# Buzzer_Card.net
KiCad netlist of a schematic drawn in EAGLE
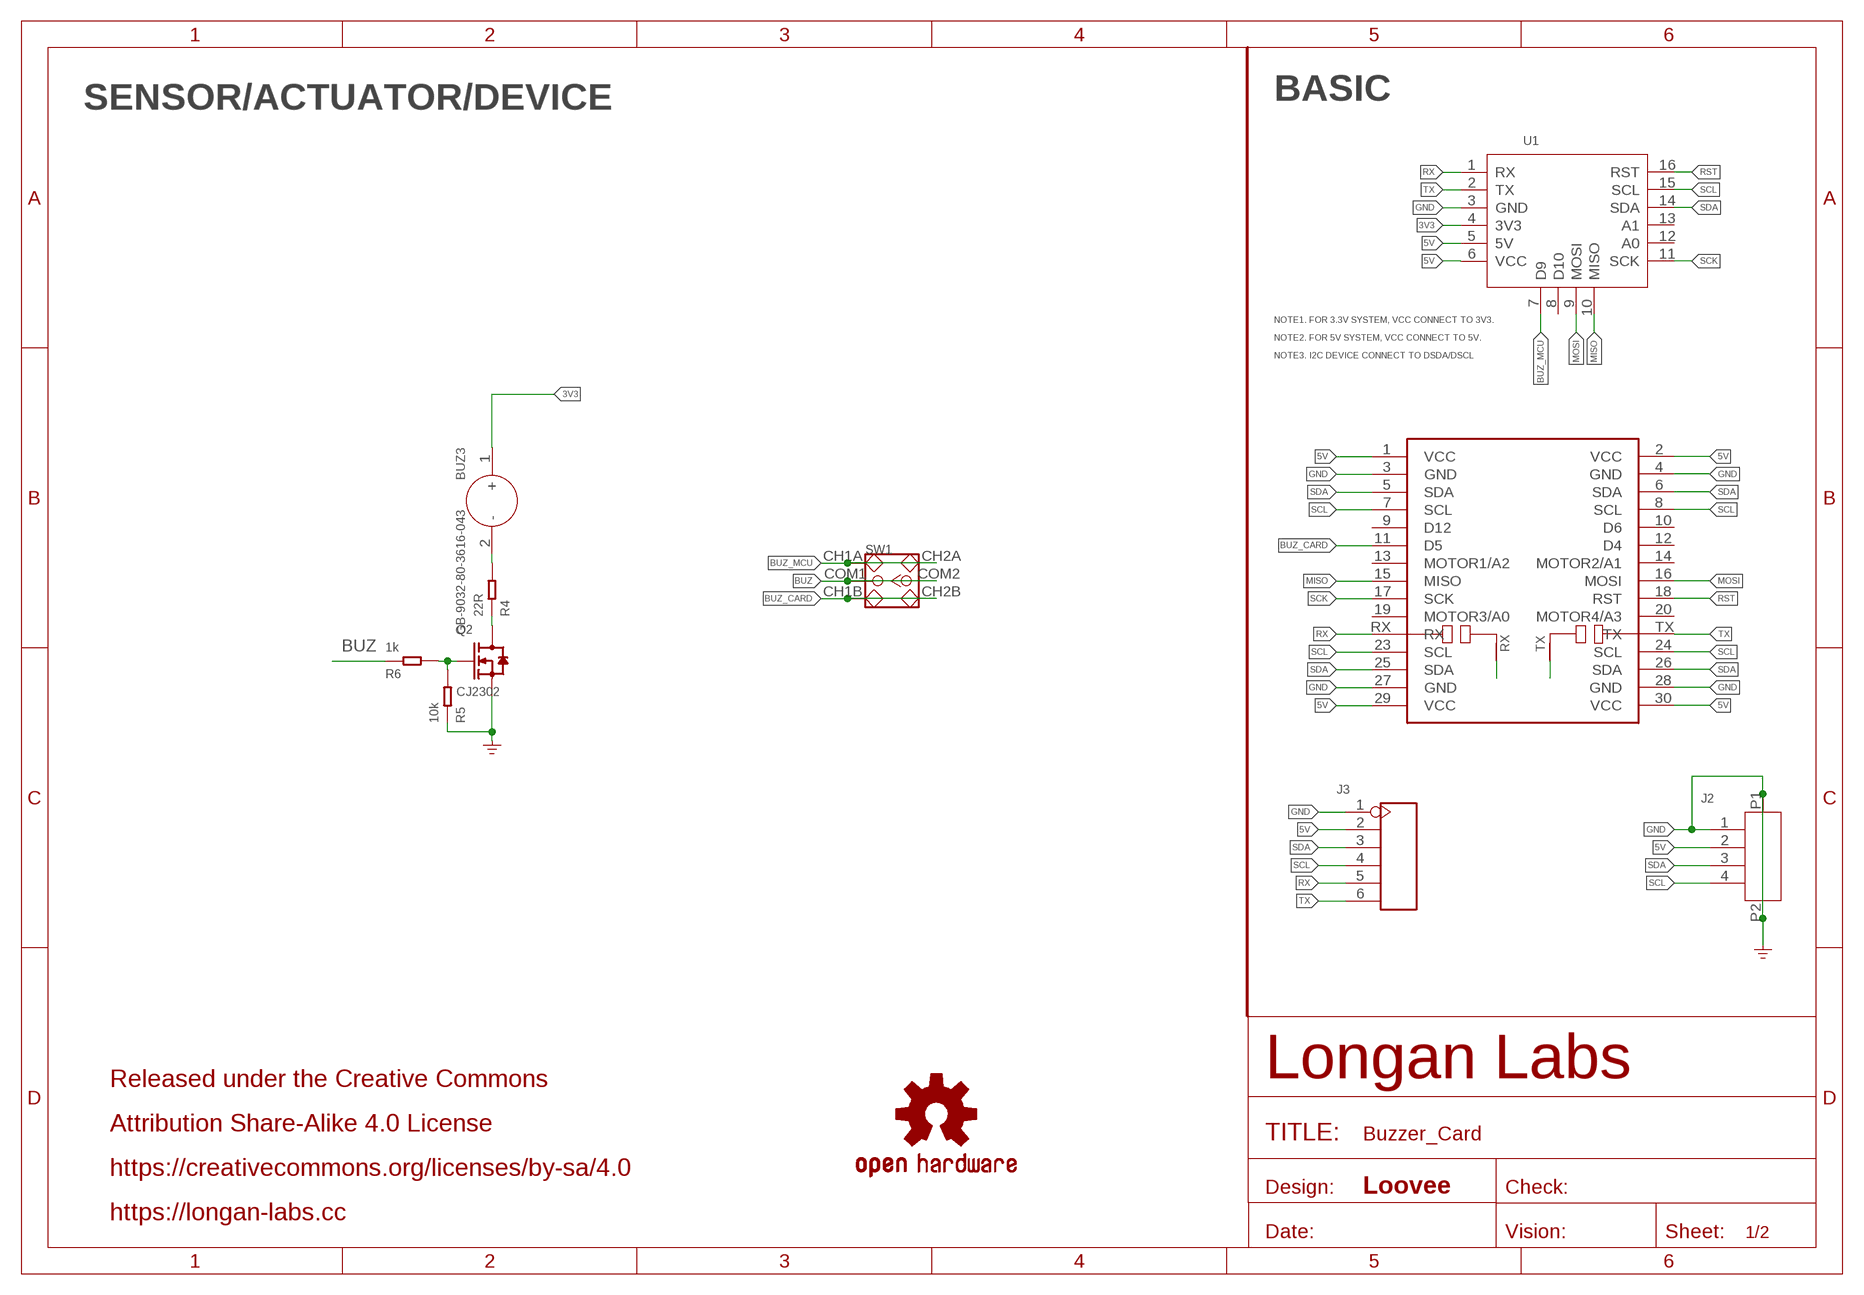
[diagram p0: schematic, sheet 1]

(export (version "E")
  (design (tool "Eeschema 10.0.6"))
  (components
    (comp (ref "BUZ3")
      (value "GB-9032-80-3616-043")
      (footprint "eagle-import:BZ2-SMD-9X10.6X3.2MM")
      (libsource (lib "eagle-import") (part "BUZZER-9X3.2MM"))
    )
    (comp (ref "J2")
      (value "HEADER-4P-1.0")
      (footprint "eagle-import:4P-1.0-90D")
      (libsource (lib "eagle-import") (part "HEADER-4P-1.0"))
    )
    (comp (ref "J3")
      (value "HEADER-6P-55/35MIL")
      (footprint "eagle-import:H6-2.54")
      (libsource (lib "eagle-import") (part "HEADER-6P-55/35MIL"))
    )
    (comp (ref "LOGO2")
      (value "OSHW-LOGOS")
      (footprint "eagle-import:OSHW-LOGO-S")
      (libsource (lib "eagle-import") (part "OSHW-LOGOS"))
    )
    (comp (ref "MOUDLE2")
      (value "MOUDLE-CARDS-UART'BOARD'")
      (footprint "eagle-import:MOUDLE-2X15P-UART")
      (libsource (lib "eagle-import") (part "MOUDLE-CARDS-UART'BOARD'"))
    )
    (comp (ref "Q2")
      (value "CJ2302")
      (footprint "eagle-import:SOT-23")
      (libsource (lib "eagle-import") (part "MOSFET-N'SOT23'"))
    )
    (comp (ref "R4")
      (value "22R")
      (footprint "eagle-import:R0603")
      (libsource (lib "eagle-import") (part "RES-0603"))
    )
    (comp (ref "R5")
      (value "10k")
      (footprint "eagle-import:R0603")
      (libsource (lib "eagle-import") (part "RES-0603"))
    )
    (comp (ref "R6")
      (value "1k")
      (footprint "eagle-import:R0603")
      (libsource (lib "eagle-import") (part "RES-0603"))
    )
    (comp (ref "SW1")
      (value "SWITCH-2CH-6P-SMD")
      (footprint "eagle-import:SW6-2.54-SMD-7.0X3.5X1.5MM")
      (libsource (lib "eagle-import") (part "SWITCH-2CH-6P-SMD"))
    )
    (comp (ref "U1")
      (value "MOUDLE-CARDS")
      (footprint "eagle-import:16P-2.0-CARDS")
      (libsource (lib "eagle-import") (part "MOUDLE-CARDS"))
    )
  )
  (nets
    (net (code "1") (name "3V3") (class "Default")
      (node (ref "BUZ3") (pin "1") (pinfunction "+_1") (pintype "bidirectional"))
      (node (ref "U1") (pin "4") (pinfunction "3V3_4") (pintype "bidirectional"))
    )
    (net (code "2") (name "5V") (class "Default")
      (node (ref "J2") (pin "2") (pinfunction "2_2") (pintype "bidirectional"))
      (node (ref "J3") (pin "2") (pinfunction "2_2") (pintype "bidirectional"))
      (node (ref "MOUDLE2") (pin "1") (pinfunction "VCC_1") (pintype "bidirectional"))
      (node (ref "MOUDLE2") (pin "2") (pinfunction "VCC_2") (pintype "bidirectional"))
      (node (ref "MOUDLE2") (pin "29") (pinfunction "VCC_29") (pintype "bidirectional"))
      (node (ref "MOUDLE2") (pin "30") (pinfunction "VCC_30") (pintype "bidirectional"))
      (node (ref "U1") (pin "5") (pinfunction "5V_5") (pintype "bidirectional"))
      (node (ref "U1") (pin "6") (pinfunction "VCC_6") (pintype "bidirectional"))
    )
    (net (code "3") (name "BUZ") (class "Default")
      (node (ref "R6") (pin "1") (pinfunction "1_1") (pintype "passive"))
      (node (ref "SW1") (pin "COM1") (pinfunction "COM1_COM1") (pintype "bidirectional"))
      (node (ref "SW1") (pin "COM2") (pinfunction "COM2_COM2") (pintype "bidirectional"))
    )
    (net (code "4") (name "BUZ_CARD") (class "Default")
      (node (ref "MOUDLE2") (pin "11") (pinfunction "D5_11") (pintype "bidirectional"))
      (node (ref "SW1") (pin "CH1B") (pinfunction "CH1B_CH1B") (pintype "bidirectional"))
      (node (ref "SW1") (pin "CH2B") (pinfunction "CH2B_CH2B") (pintype "bidirectional"))
    )
    (net (code "5") (name "BUZ_MCU") (class "Default")
      (node (ref "SW1") (pin "CH1A") (pinfunction "CH1A_CH1A") (pintype "bidirectional"))
      (node (ref "SW1") (pin "CH2A") (pinfunction "CH2A_CH2A") (pintype "bidirectional"))
      (node (ref "U1") (pin "7") (pinfunction "D9_7") (pintype "bidirectional"))
    )
    (net (code "6") (name "GND") (class "Default")
      (node (ref "J2") (pin "1") (pinfunction "1_1") (pintype "bidirectional"))
      (node (ref "J2") (pin "P1") (pinfunction "P1_P1") (pintype "bidirectional"))
      (node (ref "J2") (pin "P2") (pinfunction "P2_P2") (pintype "bidirectional"))
      (node (ref "J3") (pin "1") (pinfunction "1_1") (pintype "bidirectional"))
      (node (ref "MOUDLE2") (pin "27") (pinfunction "GND_27") (pintype "bidirectional"))
      (node (ref "MOUDLE2") (pin "28") (pinfunction "GND_28") (pintype "bidirectional"))
      (node (ref "MOUDLE2") (pin "3") (pinfunction "GND_3") (pintype "bidirectional"))
      (node (ref "MOUDLE2") (pin "4") (pinfunction "GND_4") (pintype "bidirectional"))
      (node (ref "Q2") (pin "2") (pinfunction "S_2") (pintype "passive"))
      (node (ref "R5") (pin "1") (pinfunction "1_1") (pintype "passive"))
      (node (ref "U1") (pin "3") (pinfunction "GND_3") (pintype "bidirectional"))
    )
    (net (code "7") (name "MISO") (class "Default")
      (node (ref "MOUDLE2") (pin "15") (pinfunction "MISO_15") (pintype "bidirectional"))
      (node (ref "U1") (pin "10") (pinfunction "MISO_10") (pintype "bidirectional"))
    )
    (net (code "8") (name "MOSI") (class "Default")
      (node (ref "MOUDLE2") (pin "16") (pinfunction "MOSI_16") (pintype "bidirectional"))
      (node (ref "U1") (pin "9") (pinfunction "MOSI_9") (pintype "bidirectional"))
    )
    (net (code "9") (name "Net-(BUZ3--)") (class "Default")
      (node (ref "BUZ3") (pin "2") (pinfunction "-_2") (pintype "bidirectional"))
      (node (ref "R4") (pin "2") (pinfunction "2_2") (pintype "passive"))
    )
    (net (code "10") (name "Net-(MOUDLE2-RX{slash}N-PadRX{slash}N1)") (class "Default")
      (node (ref "MOUDLE2") (pin "RX/N1") (pinfunction "RX/N_RX/N1") (pintype "bidirectional"))
      (node (ref "MOUDLE2") (pin "RX/N2") (pinfunction "RX/N_RX/N2") (pintype "bidirectional"))
    )
    (net (code "11") (name "Net-(MOUDLE2-TX{slash}N-PadTX{slash}N1)") (class "Default")
      (node (ref "MOUDLE2") (pin "TX/N1") (pinfunction "TX/N_TX/N1") (pintype "bidirectional"))
      (node (ref "MOUDLE2") (pin "TX/N2") (pinfunction "TX/N_TX/N2") (pintype "bidirectional"))
    )
    (net (code "12") (name "Net-(Q2-D)") (class "Default")
      (node (ref "Q2") (pin "3") (pinfunction "D_3") (pintype "passive"))
      (node (ref "R4") (pin "1") (pinfunction "1_1") (pintype "passive"))
    )
    (net (code "13") (name "Net-(Q2-G)") (class "Default")
      (node (ref "Q2") (pin "1") (pinfunction "G_1") (pintype "passive"))
      (node (ref "R5") (pin "2") (pinfunction "2_2") (pintype "passive"))
      (node (ref "R6") (pin "2") (pinfunction "2_2") (pintype "passive"))
    )
    (net (code "14") (name "RST") (class "Default")
      (node (ref "MOUDLE2") (pin "18") (pinfunction "RST_18") (pintype "bidirectional"))
      (node (ref "U1") (pin "16") (pinfunction "RST_16") (pintype "bidirectional"))
    )
    (net (code "15") (name "RX") (class "Default")
      (node (ref "J3") (pin "5") (pinfunction "5_5") (pintype "bidirectional"))
      (node (ref "MOUDLE2") (pin "RX") (pinfunction "RX_RX") (pintype "bidirectional"))
      (node (ref "U1") (pin "1") (pinfunction "RX_1") (pintype "bidirectional"))
    )
    (net (code "16") (name "SCK") (class "Default")
      (node (ref "MOUDLE2") (pin "17") (pinfunction "SCK_17") (pintype "bidirectional"))
      (node (ref "U1") (pin "11") (pinfunction "SCK_11") (pintype "bidirectional"))
    )
    (net (code "17") (name "SCL") (class "Default")
      (node (ref "J2") (pin "4") (pinfunction "4_4") (pintype "bidirectional"))
      (node (ref "J3") (pin "4") (pinfunction "4_4") (pintype "bidirectional"))
      (node (ref "MOUDLE2") (pin "23") (pinfunction "SCL_23") (pintype "bidirectional"))
      (node (ref "MOUDLE2") (pin "24") (pinfunction "SCL_24") (pintype "bidirectional"))
      (node (ref "MOUDLE2") (pin "7") (pinfunction "SCL_7") (pintype "bidirectional"))
      (node (ref "MOUDLE2") (pin "8") (pinfunction "SCL_8") (pintype "bidirectional"))
      (node (ref "U1") (pin "15") (pinfunction "SCL_15") (pintype "bidirectional"))
    )
    (net (code "18") (name "SDA") (class "Default")
      (node (ref "J2") (pin "3") (pinfunction "3_3") (pintype "bidirectional"))
      (node (ref "J3") (pin "3") (pinfunction "3_3") (pintype "bidirectional"))
      (node (ref "MOUDLE2") (pin "25") (pinfunction "SDA_25") (pintype "bidirectional"))
      (node (ref "MOUDLE2") (pin "26") (pinfunction "SDA_26") (pintype "bidirectional"))
      (node (ref "MOUDLE2") (pin "5") (pinfunction "SDA_5") (pintype "bidirectional"))
      (node (ref "MOUDLE2") (pin "6") (pinfunction "SDA_6") (pintype "bidirectional"))
      (node (ref "U1") (pin "14") (pinfunction "SDA_14") (pintype "bidirectional"))
    )
    (net (code "19") (name "TX") (class "Default")
      (node (ref "J3") (pin "6") (pinfunction "6_6") (pintype "bidirectional"))
      (node (ref "MOUDLE2") (pin "TX") (pinfunction "TX_TX") (pintype "bidirectional"))
      (node (ref "U1") (pin "2") (pinfunction "TX_2") (pintype "bidirectional"))
    )
    (net (code "20") (name "unconnected-(MOUDLE2-D4-Pad12)") (class "Default")
      (node (ref "MOUDLE2") (pin "12") (pinfunction "D4_12") (pintype "bidirectional"))
    )
    (net (code "21") (name "unconnected-(MOUDLE2-D6-Pad10)") (class "Default")
      (node (ref "MOUDLE2") (pin "10") (pinfunction "D6_10") (pintype "bidirectional"))
    )
    (net (code "22") (name "unconnected-(MOUDLE2-D12-Pad9)") (class "Default")
      (node (ref "MOUDLE2") (pin "9") (pinfunction "D12_9") (pintype "bidirectional"))
    )
    (net (code "23") (name "unconnected-(MOUDLE2-MOTOR1{slash}A2-Pad13)") (class "Default")
      (node (ref "MOUDLE2") (pin "13") (pinfunction "MOTOR1/A2_13") (pintype "bidirectional"))
    )
    (net (code "24") (name "unconnected-(MOUDLE2-MOTOR2{slash}A1-Pad14)") (class "Default")
      (node (ref "MOUDLE2") (pin "14") (pinfunction "MOTOR2/A1_14") (pintype "bidirectional"))
    )
    (net (code "25") (name "unconnected-(MOUDLE2-MOTOR3{slash}A0-Pad19)") (class "Default")
      (node (ref "MOUDLE2") (pin "19") (pinfunction "MOTOR3/A0_19") (pintype "bidirectional"))
    )
    (net (code "26") (name "unconnected-(MOUDLE2-MOTOR4{slash}A3-Pad20)") (class "Default")
      (node (ref "MOUDLE2") (pin "20") (pinfunction "MOTOR4/A3_20") (pintype "bidirectional"))
    )
    (net (code "27") (name "unconnected-(U1-A0-Pad12)") (class "Default")
      (node (ref "U1") (pin "12") (pinfunction "A0_12") (pintype "bidirectional"))
    )
    (net (code "28") (name "unconnected-(U1-A1-Pad13)") (class "Default")
      (node (ref "U1") (pin "13") (pinfunction "A1_13") (pintype "bidirectional"))
    )
    (net (code "29") (name "unconnected-(U1-D10-Pad8)") (class "Default")
      (node (ref "U1") (pin "8") (pinfunction "D10_8") (pintype "bidirectional"))
    )
  )
)
